# Barometer.net
KiCad netlist of a schematic drawn in Altium Designer
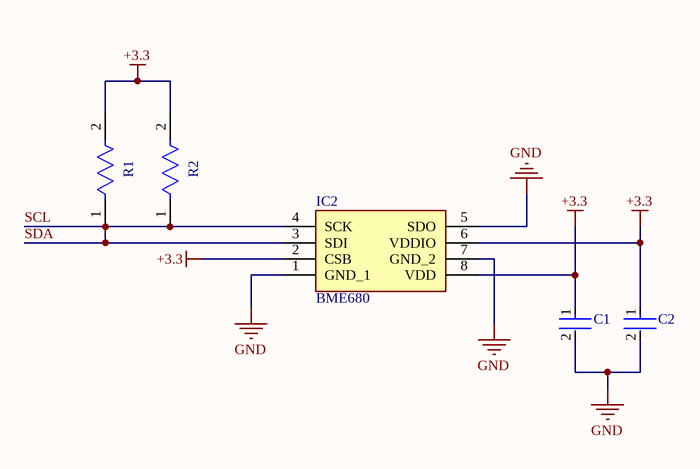
[diagram p0: Barometer.SchDoc]

(export (version "E")
  (design (tool "Eeschema 10.0.6"))
  (components
    (comp (ref "C1")
      (value "CC0402KRX7R7BB104")
      (footprint "FP-CC0402-MFG")
      (description "CAP CER 0.1UF 16V X7R 0402")
      (fields (field (name "MANUFACTURER") "YAGEO") (field (name "TOLERANCE") "0.1"))
      (libsource (lib "Altium Content Vault") (part "11868f565c42a9108669ba33697ecf6"))
    )
    (comp (ref "C2")
      (value "CC0402KRX7R7BB104")
      (footprint "FP-CC0402-MFG")
      (description "CAP CER 0.1UF 16V X7R 0402")
      (fields (field (name "MANUFACTURER") "YAGEO") (field (name "TOLERANCE") "0.1"))
      (libsource (lib "Altium Content Vault") (part "11868f565c42a9108669ba33697ecf6"))
    )
    (comp (ref "IC2")
      (value "BME680")
      (footprint "SamacSys:BME680")
      (description "Integrated Circuit")
      (fields (field (name "MOUSER PART NUMBER") "262-BME680"))
      (libsource (lib "SamacSys") (part "BME680"))
    )
    (comp (ref "R1")
      (value "AC1206JR-074K7L")
      (footprint "FP-AC1206-MFG")
      (description "RES SMD 4.7K OHM 5% 1/4W 1206")
      (fields
        (field (name "OCTOPART") "https://octopart.com/ac1206jr-074k7l-yageo-30511310")
        (field (name "TOLERANCE") "0.05")
      )
      (libsource (lib "Altium Content Vault") (part "1029c3af85768c4190bb7ad29bc67b5"))
    )
    (comp (ref "R2")
      (value "AC1206JR-074K7L")
      (footprint "FP-AC1206-MFG")
      (description "RES SMD 4.7K OHM 5% 1/4W 1206")
      (fields
        (field (name "OCTOPART") "https://octopart.com/ac1206jr-074k7l-yageo-30511310")
        (field (name "TOLERANCE") "0.05")
      )
      (libsource (lib "Altium Content Vault") (part "1029c3af85768c4190bb7ad29bc67b5"))
    )
  )
  (nets
    (net (code "1") (name "+3.3") (class "Default")
      (node (ref "C1") (pin "1") (pinfunction "1_1") (pintype "passive"))
      (node (ref "C2") (pin "1") (pinfunction "1_1") (pintype "passive"))
      (node (ref "IC2") (pin "2") (pinfunction "CSB_2") (pintype "passive"))
      (node (ref "IC2") (pin "6") (pinfunction "VDDIO_6") (pintype "passive"))
      (node (ref "IC2") (pin "8") (pinfunction "VDD_8") (pintype "passive"))
      (node (ref "R1") (pin "2") (pinfunction "2_2") (pintype "passive"))
      (node (ref "R2") (pin "2") (pinfunction "2_2") (pintype "passive"))
    )
    (net (code "2") (name "/SCL") (class "Default")
      (node (ref "IC2") (pin "3") (pinfunction "SDI_3") (pintype "passive"))
      (node (ref "IC2") (pin "4") (pinfunction "SCK_4") (pintype "passive"))
      (node (ref "R1") (pin "1") (pinfunction "1_1") (pintype "passive"))
      (node (ref "R2") (pin "1") (pinfunction "1_1") (pintype "passive"))
    )
    (net (code "3") (name "GND") (class "Default")
      (node (ref "C1") (pin "2") (pinfunction "2_2") (pintype "passive"))
      (node (ref "C2") (pin "2") (pinfunction "2_2") (pintype "passive"))
      (node (ref "IC2") (pin "1") (pinfunction "GND_1_1") (pintype "passive"))
      (node (ref "IC2") (pin "5") (pinfunction "SDO_5") (pintype "passive"))
      (node (ref "IC2") (pin "7") (pinfunction "GND_2_7") (pintype "passive"))
    )
  )
)
